# OSPLC2_2_IO2.net
KiCad netlist of a schematic drawn in Altium Designer
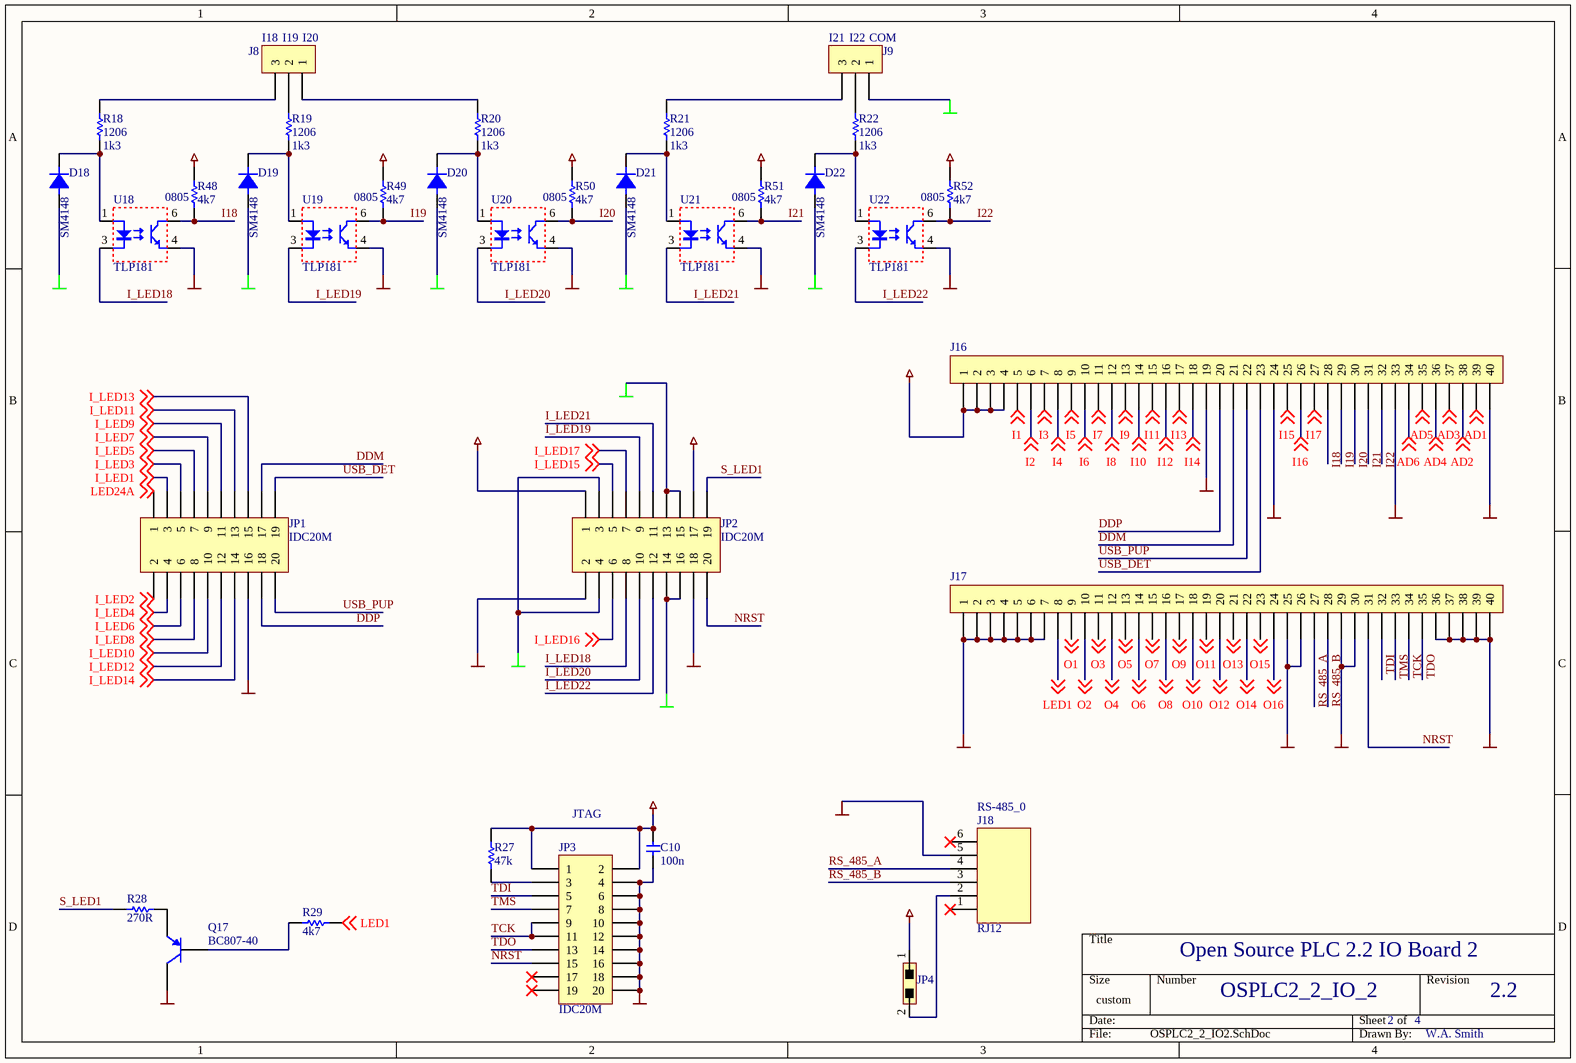
[diagram p0: OSPLC2_2_IO2.SchDoc]

(export (version "E")
  (design (tool "Eeschema 10.0.6"))
  (components
    (comp (ref "C10")
      (value "0603")
      (footprint "0603")
      (description "0603 footprint non-polorised capacitor")
      (fields (field (name "ALTIUM_VALUE") "100n"))
      (libsource (lib "Integrated Comp_lib") (part "CAP_0603"))
    )
    (comp (ref "D18")
      (value "SM4148")
      (footprint "MELF-R2/X1.6")
      (description "SMT 1N4148 diode")
      (libsource (lib "ARM_projects") (part "SM4148"))
    )
    (comp (ref "D19")
      (value "SM4148")
      (footprint "MELF-R2/X1.6")
      (description "SMT 1N4148 diode")
      (libsource (lib "ARM_projects") (part "SM4148"))
    )
    (comp (ref "D20")
      (value "SM4148")
      (footprint "MELF-R2/X1.6")
      (description "SMT 1N4148 diode")
      (libsource (lib "ARM_projects") (part "SM4148"))
    )
    (comp (ref "D21")
      (value "SM4148")
      (footprint "MELF-R2/X1.6")
      (description "SMT 1N4148 diode")
      (libsource (lib "ARM_projects") (part "SM4148"))
    )
    (comp (ref "D22")
      (value "SM4148")
      (footprint "MELF-R2/X1.6")
      (description "SMT 1N4148 diode")
      (libsource (lib "ARM_projects") (part "SM4148"))
    )
    (comp (ref "J8")
      (value "PCB TERMINAL")
      (footprint "TERMINAL_3WAY_5MM")
      (description "5mm spaced PCB terminal, 3 pole")
      (libsource (lib "ARM_projects") (part "TERMINAL_3WAY_5MM"))
    )
    (comp (ref "J9")
      (value "PCB TERMINAL")
      (footprint "TERMINAL_3WAY_5MM")
      (description "5mm spaced PCB terminal, 3 pole")
      (libsource (lib "ARM_projects") (part "TERMINAL_3WAY_5MM"))
    )
    (comp (ref "J16")
      (value "HEADER 1 x 40")
      (footprint "HEADER_1_40")
      (description "2.54mm header, 1 by 40")
      (libsource (lib "ARM_projects") (part "HEADER_1_40"))
    )
    (comp (ref "J17")
      (value "HEADER 1 x 40")
      (footprint "HEADER_1_40")
      (description "2.54mm header, 1 by 40")
      (libsource (lib "ARM_projects") (part "HEADER_1_40"))
    )
    (comp (ref "J18")
      (value "RJ12")
      (footprint "RJ-12-95001-2661")
      (description "RJ 12 Socket, Molex Part num. 95001-2661")
      (libsource (lib "ARM_projects") (part "RJ-12-95001-2661"))
    )
    (comp (ref "JP1")
      (value "IDC20M")
      (footprint "IDC_20M_BOX")
      (description "20 pin IDC male connector, vertical, box")
      (libsource (lib "") (part "IDC_20M_1"))
    )
    (comp (ref "JP2")
      (value "IDC20M")
      (footprint "IDC_20M_BOX")
      (description "20 pin IDC male connector, vertical, box")
      (libsource (lib "") (part "IDC_20M_1"))
    )
    (comp (ref "JP3")
      (value "IDC20M")
      (footprint "IDC_20M_BOX")
      (description "20 pin IDC male connector, vertical, box")
      (libsource (lib "ARM_projects") (part "IDC_20M"))
    )
    (comp (ref "JP4")
      (value "JUMPER2")
      (footprint "JUMPER2_254")
      (description "2 Pin Jumper, 2.54mm")
      (libsource (lib "ARM_projects") (part "JUMPER2"))
    )
    (comp (ref "Q17")
      (value "BC807-40")
      (footprint "SO-G3/Y1")
      (description "PNP General Purpose Amplifier")
      (fields
        (field (name "MANUFACTURER") "Fairchild Semiconductor")
        (field (name "PUBLISHER") "Altium Limited")
      )
      (libsource (lib "FSC Discrete BJT") (part "BC807-40"))
    )
    (comp (ref "R18")
      (value "1206")
      (footprint "1206")
      (description "1206 footprint resistor")
      (fields (field (name "ALTIUM_VALUE") "1k3"))
      (libsource (lib "Integrated Comp_lib") (part "RES_1206"))
    )
    (comp (ref "R19")
      (value "1206")
      (footprint "1206")
      (description "1206 footprint resistor")
      (fields (field (name "ALTIUM_VALUE") "1k3"))
      (libsource (lib "Integrated Comp_lib") (part "RES_1206"))
    )
    (comp (ref "R20")
      (value "1206")
      (footprint "1206")
      (description "1206 footprint resistor")
      (fields (field (name "ALTIUM_VALUE") "1k3"))
      (libsource (lib "Integrated Comp_lib") (part "RES_1206"))
    )
    (comp (ref "R21")
      (value "1206")
      (footprint "1206")
      (description "1206 footprint resistor")
      (fields (field (name "ALTIUM_VALUE") "1k3"))
      (libsource (lib "Integrated Comp_lib") (part "RES_1206"))
    )
    (comp (ref "R22")
      (value "1206")
      (footprint "1206")
      (description "1206 footprint resistor")
      (fields (field (name "ALTIUM_VALUE") "1k3"))
      (libsource (lib "Integrated Comp_lib") (part "RES_1206"))
    )
    (comp (ref "R27")
      (value "0805")
      (footprint "0805")
      (description "0805 footprint resistor")
      (fields (field (name "ALTIUM_VALUE") "47k"))
      (libsource (lib "Integrated Comp_lib") (part "RES_0805"))
    )
    (comp (ref "R28")
      (value "0805")
      (footprint "0805")
      (description "0805 footprint resistor")
      (fields (field (name "ALTIUM_VALUE") "270R"))
      (libsource (lib "Integrated Comp_lib") (part "RES_0805"))
    )
    (comp (ref "R29")
      (value "0805")
      (footprint "0805")
      (description "0805 footprint resistor")
      (fields (field (name "ALTIUM_VALUE") "4k7"))
      (libsource (lib "Integrated Comp_lib") (part "RES_0805"))
    )
    (comp (ref "R48")
      (value "0805")
      (footprint "0805")
      (description "0805 footprint resistor")
      (fields (field (name "ALTIUM_VALUE") "4k7"))
      (libsource (lib "Integrated Comp_lib") (part "RES_0805"))
    )
    (comp (ref "R49")
      (value "0805")
      (footprint "0805")
      (description "0805 footprint resistor")
      (fields (field (name "ALTIUM_VALUE") "4k7"))
      (libsource (lib "Integrated Comp_lib") (part "RES_0805"))
    )
    (comp (ref "R50")
      (value "0805")
      (footprint "0805")
      (description "0805 footprint resistor")
      (fields (field (name "ALTIUM_VALUE") "4k7"))
      (libsource (lib "Integrated Comp_lib") (part "RES_0805"))
    )
    (comp (ref "R51")
      (value "0805")
      (footprint "0805")
      (description "0805 footprint resistor")
      (fields (field (name "ALTIUM_VALUE") "4k7"))
      (libsource (lib "Integrated Comp_lib") (part "RES_0805"))
    )
    (comp (ref "R52")
      (value "0805")
      (footprint "0805")
      (description "0805 footprint resistor")
      (fields (field (name "ALTIUM_VALUE") "4k7"))
      (libsource (lib "Integrated Comp_lib") (part "RES_0805"))
    )
    (comp (ref "U18")
      (value "TLP181")
      (footprint "SOP4_2.54")
      (description "Toshiba Photocoupler")
      (libsource (lib "Integrated Comp_lib") (part "TLP181"))
    )
    (comp (ref "U19")
      (value "TLP181")
      (footprint "SOP4_2.54")
      (description "Toshiba Photocoupler")
      (libsource (lib "Integrated Comp_lib") (part "TLP181"))
    )
    (comp (ref "U20")
      (value "TLP181")
      (footprint "SOP4_2.54")
      (description "Toshiba Photocoupler")
      (libsource (lib "Integrated Comp_lib") (part "TLP181"))
    )
    (comp (ref "U21")
      (value "TLP181")
      (footprint "SOP4_2.54")
      (description "Toshiba Photocoupler")
      (libsource (lib "Integrated Comp_lib") (part "TLP181"))
    )
    (comp (ref "U22")
      (value "TLP181")
      (footprint "SOP4_2.54")
      (description "Toshiba Photocoupler")
      (libsource (lib "Integrated Comp_lib") (part "TLP181"))
    )
  )
  (nets
    (net (code "1") (name "/DDM") (class "Default")
      (node (ref "J16") (pin "21") (pinfunction "21_21") (pintype "passive"))
      (node (ref "JP1") (pin "17") (pinfunction "17_17") (pintype "passive"))
    )
    (net (code "2") (name "/DDP") (class "Default")
      (node (ref "J16") (pin "20") (pinfunction "20_20") (pintype "passive"))
      (node (ref "JP1") (pin "18") (pinfunction "18_18") (pintype "passive"))
    )
    (net (code "3") (name "/I18") (class "Default")
      (node (ref "J16") (pin "28") (pinfunction "28_28") (pintype "passive"))
      (node (ref "R48") (pin "1") (pinfunction "1_1") (pintype "passive"))
      (node (ref "U18") (pin "6") (pinfunction "6_6") (pintype "passive"))
    )
    (net (code "4") (name "/I19") (class "Default")
      (node (ref "J16") (pin "29") (pinfunction "29_29") (pintype "passive"))
      (node (ref "R49") (pin "1") (pinfunction "1_1") (pintype "passive"))
      (node (ref "U19") (pin "6") (pinfunction "6_6") (pintype "passive"))
    )
    (net (code "5") (name "/I20") (class "Default")
      (node (ref "J16") (pin "30") (pinfunction "30_30") (pintype "passive"))
      (node (ref "R50") (pin "1") (pinfunction "1_1") (pintype "passive"))
      (node (ref "U20") (pin "6") (pinfunction "6_6") (pintype "passive"))
    )
    (net (code "6") (name "/I21") (class "Default")
      (node (ref "J16") (pin "31") (pinfunction "31_31") (pintype "passive"))
      (node (ref "R51") (pin "1") (pinfunction "1_1") (pintype "passive"))
      (node (ref "U21") (pin "6") (pinfunction "6_6") (pintype "passive"))
    )
    (net (code "7") (name "/I22") (class "Default")
      (node (ref "J16") (pin "32") (pinfunction "32_32") (pintype "passive"))
      (node (ref "R52") (pin "1") (pinfunction "1_1") (pintype "passive"))
      (node (ref "U22") (pin "6") (pinfunction "6_6") (pintype "passive"))
    )
    (net (code "8") (name "/I_LED18") (class "Default")
      (node (ref "JP2") (pin "8") (pinfunction "8_8") (pintype "passive"))
      (node (ref "U18") (pin "3") (pinfunction "3_3") (pintype "passive"))
    )
    (net (code "9") (name "/I_LED19") (class "Default")
      (node (ref "JP2") (pin "9") (pinfunction "9_9") (pintype "passive"))
      (node (ref "U19") (pin "3") (pinfunction "3_3") (pintype "passive"))
    )
    (net (code "10") (name "/I_LED20") (class "Default")
      (node (ref "JP2") (pin "10") (pinfunction "10_10") (pintype "passive"))
      (node (ref "U20") (pin "3") (pinfunction "3_3") (pintype "passive"))
    )
    (net (code "11") (name "/I_LED21") (class "Default")
      (node (ref "JP2") (pin "11") (pinfunction "11_11") (pintype "passive"))
      (node (ref "U21") (pin "3") (pinfunction "3_3") (pintype "passive"))
    )
    (net (code "12") (name "/I_LED22") (class "Default")
      (node (ref "JP2") (pin "12") (pinfunction "12_12") (pintype "passive"))
      (node (ref "U22") (pin "3") (pinfunction "3_3") (pintype "passive"))
    )
    (net (code "13") (name "/NRST") (class "Default")
      (node (ref "J17") (pin "31") (pinfunction "31_31") (pintype "passive"))
      (node (ref "JP2") (pin "20") (pinfunction "20_20") (pintype "passive"))
      (node (ref "JP3") (pin "15") (pinfunction "15_15") (pintype "passive"))
    )
    (net (code "14") (name "/RS_485_A") (class "Default")
      (node (ref "J17") (pin "27") (pinfunction "27_27") (pintype "passive"))
      (node (ref "J18") (pin "4") (pinfunction "4_4") (pintype "passive"))
    )
    (net (code "15") (name "/RS_485_B") (class "Default")
      (node (ref "J17") (pin "28") (pinfunction "28_28") (pintype "passive"))
      (node (ref "J18") (pin "3") (pinfunction "3_3") (pintype "passive"))
    )
    (net (code "16") (name "/S_LED1") (class "Default")
      (node (ref "JP2") (pin "19") (pinfunction "19_19") (pintype "passive"))
      (node (ref "R28") (pin "1") (pinfunction "1_1") (pintype "passive"))
    )
    (net (code "17") (name "/TCK") (class "Default")
      (node (ref "J17") (pin "34") (pinfunction "34_34") (pintype "passive"))
      (node (ref "JP3") (pin "11") (pinfunction "11_11") (pintype "passive"))
      (node (ref "JP3") (pin "9") (pinfunction "9_9") (pintype "passive"))
    )
    (net (code "18") (name "/TDI") (class "Default")
      (node (ref "J17") (pin "32") (pinfunction "32_32") (pintype "passive"))
      (node (ref "JP3") (pin "5") (pinfunction "5_5") (pintype "passive"))
    )
    (net (code "19") (name "/TDO") (class "Default")
      (node (ref "J17") (pin "35") (pinfunction "35_35") (pintype "passive"))
      (node (ref "JP3") (pin "13") (pinfunction "13_13") (pintype "passive"))
    )
    (net (code "20") (name "/TMS") (class "Default")
      (node (ref "J17") (pin "33") (pinfunction "33_33") (pintype "passive"))
      (node (ref "JP3") (pin "7") (pinfunction "7_7") (pintype "passive"))
    )
    (net (code "21") (name "/USB_DET") (class "Default")
      (node (ref "J16") (pin "23") (pinfunction "23_23") (pintype "passive"))
      (node (ref "JP1") (pin "19") (pinfunction "19_19") (pintype "passive"))
    )
    (net (code "22") (name "/USB_PUP") (class "Default")
      (node (ref "J16") (pin "22") (pinfunction "22_22") (pintype "passive"))
      (node (ref "JP1") (pin "20") (pinfunction "20_20") (pintype "passive"))
    )
    (net (code "23") (name "AD1") (class "Default")
      (node (ref "J16") (pin "39") (pinfunction "39_39") (pintype "passive"))
    )
    (net (code "24") (name "AD2") (class "Default")
      (node (ref "J16") (pin "38") (pinfunction "38_38") (pintype "passive"))
    )
    (net (code "25") (name "AD3") (class "Default")
      (node (ref "J16") (pin "37") (pinfunction "37_37") (pintype "passive"))
    )
    (net (code "26") (name "AD4") (class "Default")
      (node (ref "J16") (pin "36") (pinfunction "36_36") (pintype "passive"))
    )
    (net (code "27") (name "AD5") (class "Default")
      (node (ref "J16") (pin "35") (pinfunction "35_35") (pintype "passive"))
    )
    (net (code "28") (name "AD6") (class "Default")
      (node (ref "J16") (pin "34") (pinfunction "34_34") (pintype "passive"))
    )
    (net (code "29") (name "GND") (class "Default")
      (node (ref "C10") (pin "2") (pinfunction "2_2") (pintype "passive"))
      (node (ref "J16") (pin "19") (pinfunction "19_19") (pintype "passive"))
      (node (ref "J16") (pin "24") (pinfunction "24_24") (pintype "passive"))
      (node (ref "J16") (pin "33") (pinfunction "33_33") (pintype "passive"))
      (node (ref "J16") (pin "40") (pinfunction "40_40") (pintype "passive"))
      (node (ref "J17") (pin "1") (pinfunction "1_1") (pintype "passive"))
      (node (ref "J17") (pin "2") (pinfunction "2_2") (pintype "passive"))
      (node (ref "J17") (pin "25") (pinfunction "25_25") (pintype "passive"))
      (node (ref "J17") (pin "26") (pinfunction "26_26") (pintype "passive"))
      (node (ref "J17") (pin "29") (pinfunction "29_29") (pintype "passive"))
      (node (ref "J17") (pin "3") (pinfunction "3_3") (pintype "passive"))
      (node (ref "J17") (pin "30") (pinfunction "30_30") (pintype "passive"))
      (node (ref "J17") (pin "36") (pinfunction "36_36") (pintype "passive"))
      (node (ref "J17") (pin "37") (pinfunction "37_37") (pintype "passive"))
      (node (ref "J17") (pin "38") (pinfunction "38_38") (pintype "passive"))
      (node (ref "J17") (pin "39") (pinfunction "39_39") (pintype "passive"))
      (node (ref "J17") (pin "4") (pinfunction "4_4") (pintype "passive"))
      (node (ref "J17") (pin "40") (pinfunction "40_40") (pintype "passive"))
      (node (ref "J17") (pin "5") (pinfunction "5_5") (pintype "passive"))
      (node (ref "J17") (pin "6") (pinfunction "6_6") (pintype "passive"))
      (node (ref "J17") (pin "7") (pinfunction "7_7") (pintype "passive"))
      (node (ref "J18") (pin "5") (pinfunction "5_5") (pintype "passive"))
      (node (ref "JP1") (pin "16") (pinfunction "16_16") (pintype "passive"))
      (node (ref "JP2") (pin "18") (pinfunction "18_18") (pintype "passive"))
      (node (ref "JP2") (pin "2") (pinfunction "2_2") (pintype "passive"))
      (node (ref "JP3") (pin "10") (pinfunction "10_10") (pintype "passive"))
      (node (ref "JP3") (pin "12") (pinfunction "12_12") (pintype "passive"))
      (node (ref "JP3") (pin "14") (pinfunction "14_14") (pintype "passive"))
      (node (ref "JP3") (pin "16") (pinfunction "16_16") (pintype "passive"))
      (node (ref "JP3") (pin "18") (pinfunction "18_18") (pintype "passive"))
      (node (ref "JP3") (pin "20") (pinfunction "20_20") (pintype "passive"))
      (node (ref "JP3") (pin "4") (pinfunction "4_4") (pintype "passive"))
      (node (ref "JP3") (pin "6") (pinfunction "6_6") (pintype "passive"))
      (node (ref "JP3") (pin "8") (pinfunction "8_8") (pintype "passive"))
      (node (ref "Q17") (pin "3") (pinfunction "C_3") (pintype "passive"))
      (node (ref "U18") (pin "4") (pinfunction "4_4") (pintype "passive"))
      (node (ref "U19") (pin "4") (pinfunction "4_4") (pintype "passive"))
      (node (ref "U20") (pin "4") (pinfunction "4_4") (pintype "passive"))
      (node (ref "U21") (pin "4") (pinfunction "4_4") (pintype "passive"))
      (node (ref "U22") (pin "4") (pinfunction "4_4") (pintype "passive"))
    )
    (net (code "30") (name "I1") (class "Default")
      (node (ref "J16") (pin "5") (pinfunction "5_5") (pintype "passive"))
    )
    (net (code "31") (name "I2") (class "Default")
      (node (ref "J16") (pin "6") (pinfunction "6_6") (pintype "passive"))
    )
    (net (code "32") (name "I3") (class "Default")
      (node (ref "J16") (pin "7") (pinfunction "7_7") (pintype "passive"))
    )
    (net (code "33") (name "I4") (class "Default")
      (node (ref "J16") (pin "8") (pinfunction "8_8") (pintype "passive"))
    )
    (net (code "34") (name "I5") (class "Default")
      (node (ref "J16") (pin "9") (pinfunction "9_9") (pintype "passive"))
    )
    (net (code "35") (name "I6") (class "Default")
      (node (ref "J16") (pin "10") (pinfunction "10_10") (pintype "passive"))
    )
    (net (code "36") (name "I7") (class "Default")
      (node (ref "J16") (pin "11") (pinfunction "11_11") (pintype "passive"))
    )
    (net (code "37") (name "I8") (class "Default")
      (node (ref "J16") (pin "12") (pinfunction "12_12") (pintype "passive"))
    )
    (net (code "38") (name "I9") (class "Default")
      (node (ref "J16") (pin "13") (pinfunction "13_13") (pintype "passive"))
    )
    (net (code "39") (name "I10") (class "Default")
      (node (ref "J16") (pin "14") (pinfunction "14_14") (pintype "passive"))
    )
    (net (code "40") (name "I11") (class "Default")
      (node (ref "J16") (pin "15") (pinfunction "15_15") (pintype "passive"))
    )
    (net (code "41") (name "I12") (class "Default")
      (node (ref "J16") (pin "16") (pinfunction "16_16") (pintype "passive"))
    )
    (net (code "42") (name "I13") (class "Default")
      (node (ref "J16") (pin "17") (pinfunction "17_17") (pintype "passive"))
    )
    (net (code "43") (name "I14") (class "Default")
      (node (ref "J16") (pin "18") (pinfunction "18_18") (pintype "passive"))
    )
    (net (code "44") (name "I15") (class "Default")
      (node (ref "J16") (pin "25") (pinfunction "25_25") (pintype "passive"))
    )
    (net (code "45") (name "I16") (class "Default")
      (node (ref "J16") (pin "26") (pinfunction "26_26") (pintype "passive"))
    )
    (net (code "46") (name "I17") (class "Default")
      (node (ref "J16") (pin "27") (pinfunction "27_27") (pintype "passive"))
    )
    (net (code "47") (name "IN_GND") (class "Default")
      (node (ref "D18") (pin "1") (pinfunction "A_1") (pintype "passive"))
      (node (ref "D19") (pin "1") (pinfunction "A_1") (pintype "passive"))
      (node (ref "D20") (pin "1") (pinfunction "A_1") (pintype "passive"))
      (node (ref "D21") (pin "1") (pinfunction "A_1") (pintype "passive"))
      (node (ref "D22") (pin "1") (pinfunction "A_1") (pintype "passive"))
      (node (ref "J9") (pin "1") (pinfunction "1_1") (pintype "passive"))
      (node (ref "JP2") (pin "13") (pinfunction "13_13") (pintype "passive"))
      (node (ref "JP2") (pin "14") (pinfunction "14_14") (pintype "passive"))
      (node (ref "JP2") (pin "15") (pinfunction "15_15") (pintype "passive"))
      (node (ref "JP2") (pin "16") (pinfunction "16_16") (pintype "passive"))
      (node (ref "JP2") (pin "3") (pinfunction "3_3") (pintype "passive"))
      (node (ref "JP2") (pin "4") (pinfunction "4_4") (pintype "passive"))
    )
    (net (code "48") (name "I_LED1") (class "Default")
      (node (ref "JP1") (pin "3") (pinfunction "3_3") (pintype "passive"))
    )
    (net (code "49") (name "I_LED2") (class "Default")
      (node (ref "JP1") (pin "2") (pinfunction "2_2") (pintype "passive"))
    )
    (net (code "50") (name "I_LED3") (class "Default")
      (node (ref "JP1") (pin "5") (pinfunction "5_5") (pintype "passive"))
    )
    (net (code "51") (name "I_LED4") (class "Default")
      (node (ref "JP1") (pin "4") (pinfunction "4_4") (pintype "passive"))
    )
    (net (code "52") (name "I_LED5") (class "Default")
      (node (ref "JP1") (pin "7") (pinfunction "7_7") (pintype "passive"))
    )
    (net (code "53") (name "I_LED6") (class "Default")
      (node (ref "JP1") (pin "6") (pinfunction "6_6") (pintype "passive"))
    )
    (net (code "54") (name "I_LED7") (class "Default")
      (node (ref "JP1") (pin "9") (pinfunction "9_9") (pintype "passive"))
    )
    (net (code "55") (name "I_LED8") (class "Default")
      (node (ref "JP1") (pin "8") (pinfunction "8_8") (pintype "passive"))
    )
    (net (code "56") (name "I_LED9") (class "Default")
      (node (ref "JP1") (pin "11") (pinfunction "11_11") (pintype "passive"))
    )
    (net (code "57") (name "I_LED10") (class "Default")
      (node (ref "JP1") (pin "10") (pinfunction "10_10") (pintype "passive"))
    )
    (net (code "58") (name "I_LED11") (class "Default")
      (node (ref "JP1") (pin "13") (pinfunction "13_13") (pintype "passive"))
    )
    (net (code "59") (name "I_LED12") (class "Default")
      (node (ref "JP1") (pin "12") (pinfunction "12_12") (pintype "passive"))
    )
    (net (code "60") (name "I_LED13") (class "Default")
      (node (ref "JP1") (pin "15") (pinfunction "15_15") (pintype "passive"))
    )
    (net (code "61") (name "I_LED14") (class "Default")
      (node (ref "JP1") (pin "14") (pinfunction "14_14") (pintype "passive"))
    )
    (net (code "62") (name "I_LED15") (class "Default")
      (node (ref "JP2") (pin "5") (pinfunction "5_5") (pintype "passive"))
    )
    (net (code "63") (name "I_LED16") (class "Default")
      (node (ref "JP2") (pin "6") (pinfunction "6_6") (pintype "passive"))
    )
    (net (code "64") (name "I_LED17") (class "Default")
      (node (ref "JP2") (pin "7") (pinfunction "7_7") (pintype "passive"))
    )
    (net (code "65") (name "LED1") (class "Default")
      (node (ref "J17") (pin "8") (pinfunction "8_8") (pintype "passive"))
      (node (ref "R29") (pin "2") (pinfunction "2_2") (pintype "passive"))
    )
    (net (code "66") (name "LED24A") (class "Default")
      (node (ref "JP1") (pin "1") (pinfunction "1_1") (pintype "passive"))
    )
    (net (code "67") (name "Net-(D18-C)") (class "Default")
      (node (ref "D18") (pin "2") (pinfunction "C_2") (pintype "passive"))
      (node (ref "R18") (pin "1") (pinfunction "1_1") (pintype "passive"))
      (node (ref "U18") (pin "1") (pinfunction "1_1") (pintype "passive"))
    )
    (net (code "68") (name "Net-(D19-C)") (class "Default")
      (node (ref "D19") (pin "2") (pinfunction "C_2") (pintype "passive"))
      (node (ref "R19") (pin "1") (pinfunction "1_1") (pintype "passive"))
      (node (ref "U19") (pin "1") (pinfunction "1_1") (pintype "passive"))
    )
    (net (code "69") (name "Net-(D20-C)") (class "Default")
      (node (ref "D20") (pin "2") (pinfunction "C_2") (pintype "passive"))
      (node (ref "R20") (pin "1") (pinfunction "1_1") (pintype "passive"))
      (node (ref "U20") (pin "1") (pinfunction "1_1") (pintype "passive"))
    )
    (net (code "70") (name "Net-(D21-C)") (class "Default")
      (node (ref "D21") (pin "2") (pinfunction "C_2") (pintype "passive"))
      (node (ref "R21") (pin "1") (pinfunction "1_1") (pintype "passive"))
      (node (ref "U21") (pin "1") (pinfunction "1_1") (pintype "passive"))
    )
    (net (code "71") (name "Net-(D22-C)") (class "Default")
      (node (ref "D22") (pin "2") (pinfunction "C_2") (pintype "passive"))
      (node (ref "R22") (pin "1") (pinfunction "1_1") (pintype "passive"))
      (node (ref "U22") (pin "1") (pinfunction "1_1") (pintype "passive"))
    )
    (net (code "72") (name "Net-(J8-Pad1)") (class "Default")
      (node (ref "J8") (pin "1") (pinfunction "1_1") (pintype "passive"))
      (node (ref "R20") (pin "2") (pinfunction "2_2") (pintype "passive"))
    )
    (net (code "73") (name "Net-(J8-Pad2)") (class "Default")
      (node (ref "J8") (pin "2") (pinfunction "2_2") (pintype "passive"))
      (node (ref "R19") (pin "2") (pinfunction "2_2") (pintype "passive"))
    )
    (net (code "74") (name "Net-(J8-Pad3)") (class "Default")
      (node (ref "J8") (pin "3") (pinfunction "3_3") (pintype "passive"))
      (node (ref "R18") (pin "2") (pinfunction "2_2") (pintype "passive"))
    )
    (net (code "75") (name "Net-(J9-Pad2)") (class "Default")
      (node (ref "J9") (pin "2") (pinfunction "2_2") (pintype "passive"))
      (node (ref "R22") (pin "2") (pinfunction "2_2") (pintype "passive"))
    )
    (net (code "76") (name "Net-(J9-Pad3)") (class "Default")
      (node (ref "J9") (pin "3") (pinfunction "3_3") (pintype "passive"))
      (node (ref "R21") (pin "2") (pinfunction "2_2") (pintype "passive"))
    )
    (net (code "77") (name "Net-(J18-Pad2)") (class "Default")
      (node (ref "J18") (pin "2") (pinfunction "2_2") (pintype "passive"))
      (node (ref "JP4") (pin "2") (pinfunction "2_2") (pintype "passive"))
    )
    (net (code "78") (name "Net-(JP3-Pad3)") (class "Default")
      (node (ref "JP3") (pin "3") (pinfunction "3_3") (pintype "passive"))
      (node (ref "R27") (pin "1") (pinfunction "1_1") (pintype "passive"))
    )
    (net (code "79") (name "Net-(Q17-B)") (class "Default")
      (node (ref "Q17") (pin "1") (pinfunction "B_1") (pintype "passive"))
      (node (ref "R29") (pin "1") (pinfunction "1_1") (pintype "passive"))
    )
    (net (code "80") (name "Net-(Q17-E)") (class "Default")
      (node (ref "Q17") (pin "2") (pinfunction "E_2") (pintype "passive"))
      (node (ref "R28") (pin "2") (pinfunction "2_2") (pintype "passive"))
    )
    (net (code "81") (name "O1") (class "Default")
      (node (ref "J17") (pin "9") (pinfunction "9_9") (pintype "passive"))
    )
    (net (code "82") (name "O2") (class "Default")
      (node (ref "J17") (pin "10") (pinfunction "10_10") (pintype "passive"))
    )
    (net (code "83") (name "O3") (class "Default")
      (node (ref "J17") (pin "11") (pinfunction "11_11") (pintype "passive"))
    )
    (net (code "84") (name "O4") (class "Default")
      (node (ref "J17") (pin "12") (pinfunction "12_12") (pintype "passive"))
    )
    (net (code "85") (name "O5") (class "Default")
      (node (ref "J17") (pin "13") (pinfunction "13_13") (pintype "passive"))
    )
    (net (code "86") (name "O6") (class "Default")
      (node (ref "J17") (pin "14") (pinfunction "14_14") (pintype "passive"))
    )
    (net (code "87") (name "O7") (class "Default")
      (node (ref "J17") (pin "15") (pinfunction "15_15") (pintype "passive"))
    )
    (net (code "88") (name "O8") (class "Default")
      (node (ref "J17") (pin "16") (pinfunction "16_16") (pintype "passive"))
    )
    (net (code "89") (name "O9") (class "Default")
      (node (ref "J17") (pin "17") (pinfunction "17_17") (pintype "passive"))
    )
    (net (code "90") (name "O10") (class "Default")
      (node (ref "J17") (pin "18") (pinfunction "18_18") (pintype "passive"))
    )
    (net (code "91") (name "O11") (class "Default")
      (node (ref "J17") (pin "19") (pinfunction "19_19") (pintype "passive"))
    )
    (net (code "92") (name "O12") (class "Default")
      (node (ref "J17") (pin "20") (pinfunction "20_20") (pintype "passive"))
    )
    (net (code "93") (name "O13") (class "Default")
      (node (ref "J17") (pin "21") (pinfunction "21_21") (pintype "passive"))
    )
    (net (code "94") (name "O14") (class "Default")
      (node (ref "J17") (pin "22") (pinfunction "22_22") (pintype "passive"))
    )
    (net (code "95") (name "O15") (class "Default")
      (node (ref "J17") (pin "23") (pinfunction "23_23") (pintype "passive"))
    )
    (net (code "96") (name "O16") (class "Default")
      (node (ref "J17") (pin "24") (pinfunction "24_24") (pintype "passive"))
    )
    (net (code "97") (name "VCC3v3") (class "Default")
      (node (ref "C10") (pin "1") (pinfunction "1_1") (pintype "passive"))
      (node (ref "J16") (pin "1") (pinfunction "1_1") (pintype "passive"))
      (node (ref "J16") (pin "2") (pinfunction "2_2") (pintype "passive"))
      (node (ref "J16") (pin "3") (pinfunction "3_3") (pintype "passive"))
      (node (ref "J16") (pin "4") (pinfunction "4_4") (pintype "passive"))
      (node (ref "JP2") (pin "1") (pinfunction "1_1") (pintype "passive"))
      (node (ref "JP2") (pin "17") (pinfunction "17_17") (pintype "passive"))
      (node (ref "JP3") (pin "1") (pinfunction "1_1") (pintype "passive"))
      (node (ref "JP3") (pin "2") (pinfunction "2_2") (pintype "passive"))
      (node (ref "R27") (pin "2") (pinfunction "2_2") (pintype "passive"))
      (node (ref "R48") (pin "2") (pinfunction "2_2") (pintype "passive"))
      (node (ref "R49") (pin "2") (pinfunction "2_2") (pintype "passive"))
      (node (ref "R50") (pin "2") (pinfunction "2_2") (pintype "passive"))
      (node (ref "R51") (pin "2") (pinfunction "2_2") (pintype "passive"))
      (node (ref "R52") (pin "2") (pinfunction "2_2") (pintype "passive"))
    )
    (net (code "98") (name "VCC5") (class "Default")
      (node (ref "JP4") (pin "1") (pinfunction "1_1") (pintype "passive"))
    )
    (net (code "99") (name "unconnected-(J18-Pad1)") (class "Default")
      (node (ref "J18") (pin "1") (pinfunction "1_1") (pintype "passive+no_connect"))
    )
    (net (code "100") (name "unconnected-(J18-Pad6)") (class "Default")
      (node (ref "J18") (pin "6") (pinfunction "6_6") (pintype "passive+no_connect"))
    )
    (net (code "101") (name "unconnected-(JP3-Pad17)") (class "Default")
      (node (ref "JP3") (pin "17") (pinfunction "17_17") (pintype "passive+no_connect"))
    )
    (net (code "102") (name "unconnected-(JP3-Pad19)") (class "Default")
      (node (ref "JP3") (pin "19") (pinfunction "19_19") (pintype "passive+no_connect"))
    )
  )
)
